# untitled.net
KiCad netlist of a schematic drawn in EAGLE
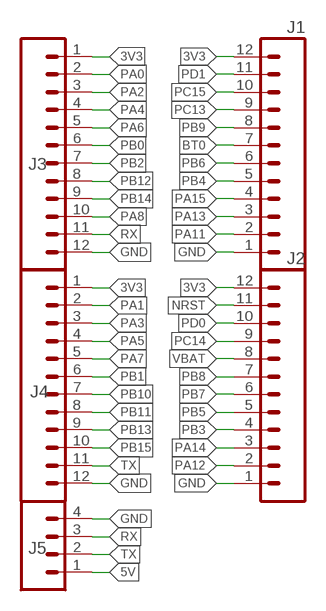
[diagram p0: schematic, sheet 1]

(export (version "E")
  (design (tool "Eeschema 10.0.6"))
  (components
    (comp (ref "J1")
      (value "M12PTH")
      (footprint "eagle-import:1X12")
      (libsource (lib "eagle-import") (part "M12PTH"))
    )
    (comp (ref "J2")
      (value "M12PTH")
      (footprint "eagle-import:1X12")
      (libsource (lib "eagle-import") (part "M12PTH"))
    )
    (comp (ref "J3")
      (value "M12PTH")
      (footprint "eagle-import:1X12")
      (libsource (lib "eagle-import") (part "M12PTH"))
    )
    (comp (ref "J4")
      (value "M12PTH")
      (footprint "eagle-import:1X12")
      (libsource (lib "eagle-import") (part "M12PTH"))
    )
    (comp (ref "J5")
      (value "M04PTH")
      (footprint "eagle-import:1X04")
      (libsource (lib "eagle-import") (part "M04PTH"))
    )
  )
  (nets
    (net (code "1") (name "3V3") (class "Default")
      (node (ref "J1") (pin "12") (pinfunction "12_12") (pintype "passive"))
      (node (ref "J2") (pin "12") (pinfunction "12_12") (pintype "passive"))
      (node (ref "J3") (pin "1") (pinfunction "1_1") (pintype "passive"))
      (node (ref "J4") (pin "1") (pinfunction "1_1") (pintype "passive"))
    )
    (net (code "2") (name "5V") (class "Default")
      (node (ref "J5") (pin "1") (pinfunction "1_1") (pintype "passive"))
    )
    (net (code "3") (name "BT0") (class "Default")
      (node (ref "J1") (pin "7") (pinfunction "7_7") (pintype "passive"))
    )
    (net (code "4") (name "GND") (class "Default")
      (node (ref "J1") (pin "1") (pinfunction "1_1") (pintype "passive"))
      (node (ref "J2") (pin "1") (pinfunction "1_1") (pintype "passive"))
      (node (ref "J3") (pin "12") (pinfunction "12_12") (pintype "passive"))
      (node (ref "J4") (pin "12") (pinfunction "12_12") (pintype "passive"))
      (node (ref "J5") (pin "4") (pinfunction "4_4") (pintype "passive"))
    )
    (net (code "5") (name "NRST") (class "Default")
      (node (ref "J2") (pin "11") (pinfunction "11_11") (pintype "passive"))
    )
    (net (code "6") (name "PA0") (class "Default")
      (node (ref "J3") (pin "2") (pinfunction "2_2") (pintype "passive"))
    )
    (net (code "7") (name "PA1") (class "Default")
      (node (ref "J4") (pin "2") (pinfunction "2_2") (pintype "passive"))
    )
    (net (code "8") (name "PA2") (class "Default")
      (node (ref "J3") (pin "3") (pinfunction "3_3") (pintype "passive"))
    )
    (net (code "9") (name "PA3") (class "Default")
      (node (ref "J4") (pin "3") (pinfunction "3_3") (pintype "passive"))
    )
    (net (code "10") (name "PA4") (class "Default")
      (node (ref "J3") (pin "4") (pinfunction "4_4") (pintype "passive"))
    )
    (net (code "11") (name "PA5") (class "Default")
      (node (ref "J4") (pin "4") (pinfunction "4_4") (pintype "passive"))
    )
    (net (code "12") (name "PA6") (class "Default")
      (node (ref "J3") (pin "5") (pinfunction "5_5") (pintype "passive"))
    )
    (net (code "13") (name "PA7") (class "Default")
      (node (ref "J4") (pin "5") (pinfunction "5_5") (pintype "passive"))
    )
    (net (code "14") (name "PA8") (class "Default")
      (node (ref "J3") (pin "10") (pinfunction "10_10") (pintype "passive"))
    )
    (net (code "15") (name "PA11") (class "Default")
      (node (ref "J1") (pin "2") (pinfunction "2_2") (pintype "passive"))
    )
    (net (code "16") (name "PA12") (class "Default")
      (node (ref "J2") (pin "2") (pinfunction "2_2") (pintype "passive"))
    )
    (net (code "17") (name "PA13") (class "Default")
      (node (ref "J1") (pin "3") (pinfunction "3_3") (pintype "passive"))
    )
    (net (code "18") (name "PA14") (class "Default")
      (node (ref "J2") (pin "3") (pinfunction "3_3") (pintype "passive"))
    )
    (net (code "19") (name "PA15") (class "Default")
      (node (ref "J1") (pin "4") (pinfunction "4_4") (pintype "passive"))
    )
    (net (code "20") (name "PB0") (class "Default")
      (node (ref "J3") (pin "6") (pinfunction "6_6") (pintype "passive"))
    )
    (net (code "21") (name "PB1") (class "Default")
      (node (ref "J4") (pin "6") (pinfunction "6_6") (pintype "passive"))
    )
    (net (code "22") (name "PB2") (class "Default")
      (node (ref "J3") (pin "7") (pinfunction "7_7") (pintype "passive"))
    )
    (net (code "23") (name "PB3") (class "Default")
      (node (ref "J2") (pin "4") (pinfunction "4_4") (pintype "passive"))
    )
    (net (code "24") (name "PB4") (class "Default")
      (node (ref "J1") (pin "5") (pinfunction "5_5") (pintype "passive"))
    )
    (net (code "25") (name "PB5") (class "Default")
      (node (ref "J2") (pin "5") (pinfunction "5_5") (pintype "passive"))
    )
    (net (code "26") (name "PB6") (class "Default")
      (node (ref "J1") (pin "6") (pinfunction "6_6") (pintype "passive"))
    )
    (net (code "27") (name "PB7") (class "Default")
      (node (ref "J2") (pin "6") (pinfunction "6_6") (pintype "passive"))
    )
    (net (code "28") (name "PB8") (class "Default")
      (node (ref "J2") (pin "7") (pinfunction "7_7") (pintype "passive"))
    )
    (net (code "29") (name "PB9") (class "Default")
      (node (ref "J1") (pin "8") (pinfunction "8_8") (pintype "passive"))
    )
    (net (code "30") (name "PB10") (class "Default")
      (node (ref "J4") (pin "7") (pinfunction "7_7") (pintype "passive"))
    )
    (net (code "31") (name "PB11") (class "Default")
      (node (ref "J4") (pin "8") (pinfunction "8_8") (pintype "passive"))
    )
    (net (code "32") (name "PB12") (class "Default")
      (node (ref "J3") (pin "8") (pinfunction "8_8") (pintype "passive"))
    )
    (net (code "33") (name "PB13") (class "Default")
      (node (ref "J4") (pin "9") (pinfunction "9_9") (pintype "passive"))
    )
    (net (code "34") (name "PB14") (class "Default")
      (node (ref "J3") (pin "9") (pinfunction "9_9") (pintype "passive"))
    )
    (net (code "35") (name "PB15") (class "Default")
      (node (ref "J4") (pin "10") (pinfunction "10_10") (pintype "passive"))
    )
    (net (code "36") (name "PC13") (class "Default")
      (node (ref "J1") (pin "9") (pinfunction "9_9") (pintype "passive"))
    )
    (net (code "37") (name "PC14") (class "Default")
      (node (ref "J2") (pin "9") (pinfunction "9_9") (pintype "passive"))
    )
    (net (code "38") (name "PC15") (class "Default")
      (node (ref "J1") (pin "10") (pinfunction "10_10") (pintype "passive"))
    )
    (net (code "39") (name "PD0") (class "Default")
      (node (ref "J2") (pin "10") (pinfunction "10_10") (pintype "passive"))
    )
    (net (code "40") (name "PD1") (class "Default")
      (node (ref "J1") (pin "11") (pinfunction "11_11") (pintype "passive"))
    )
    (net (code "41") (name "RX") (class "Default")
      (node (ref "J3") (pin "11") (pinfunction "11_11") (pintype "passive"))
      (node (ref "J5") (pin "3") (pinfunction "3_3") (pintype "passive"))
    )
    (net (code "42") (name "TX") (class "Default")
      (node (ref "J4") (pin "11") (pinfunction "11_11") (pintype "passive"))
      (node (ref "J5") (pin "2") (pinfunction "2_2") (pintype "passive"))
    )
    (net (code "43") (name "VBAT") (class "Default")
      (node (ref "J2") (pin "8") (pinfunction "8_8") (pintype "passive"))
    )
  )
)
